# MAINfin2.net
KiCad netlist of a schematic drawn in EAGLE
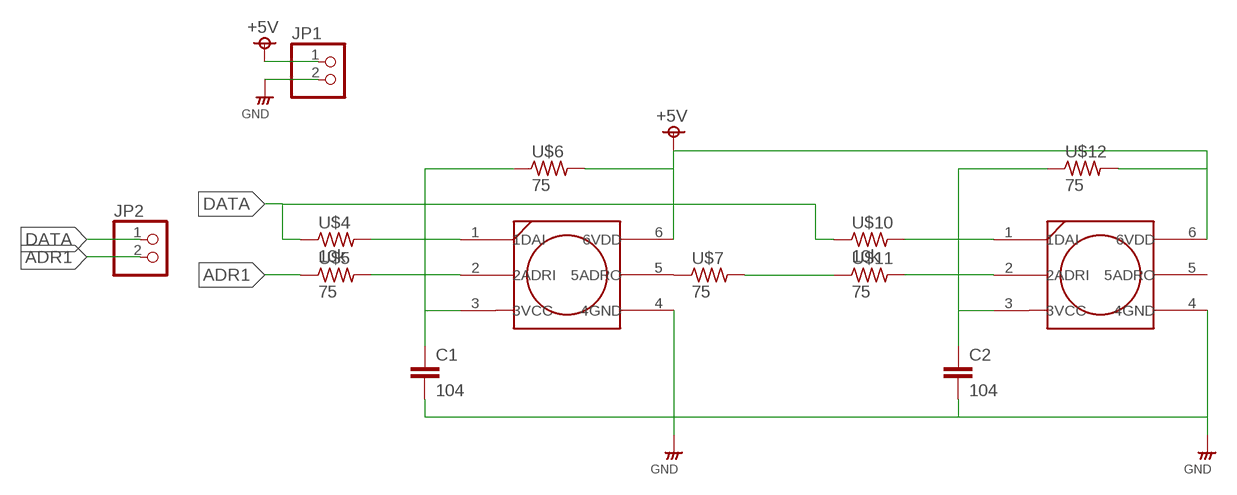
[diagram p0: schematic, sheet 1]

(export (version "E")
  (design (tool "Eeschema 10.0.6"))
  (components
    (comp (ref "C1")
      (value "104")
      (footprint "eagle-import:MLCC_25")
      (libsource (lib "eagle-import") (part "MLCC-2"))
    )
    (comp (ref "C2")
      (value "104")
      (footprint "eagle-import:MLCC_25")
      (libsource (lib "eagle-import") (part "MLCC-2"))
    )
    (comp (ref "JP1")
      (value "PINHD-1X2\"")
      (footprint "eagle-import:1_02")
      (libsource (lib "eagle-import") (part "PINHD-1X2{dblquote}"))
    )
    (comp (ref "JP2")
      (value "PINHD-1X2\"")
      (footprint "eagle-import:1_02")
      (libsource (lib "eagle-import") (part "PINHD-1X2{dblquote}"))
    )
    (comp (ref "U$1")
      (value "WS2822S")
      (footprint "eagle-import:WS2822S")
      (libsource (lib "eagle-import") (part "WS2822S"))
    )
    (comp (ref "U$4")
      (value "10k")
      (footprint "eagle-import:R_0.3")
      (libsource (lib "eagle-import") (part "RESISTORS-3"))
    )
    (comp (ref "U$5")
      (value "75")
      (footprint "eagle-import:R_0.3")
      (libsource (lib "eagle-import") (part "RESISTORS-3"))
    )
    (comp (ref "U$6")
      (value "75")
      (footprint "eagle-import:R_0.3")
      (libsource (lib "eagle-import") (part "RESISTORS-3"))
    )
    (comp (ref "U$7")
      (value "75")
      (footprint "eagle-import:R_0.3")
      (libsource (lib "eagle-import") (part "RESISTORS-3"))
    )
    (comp (ref "U$8")
      (value "WS2822S")
      (footprint "eagle-import:WS2822S")
      (libsource (lib "eagle-import") (part "WS2822S"))
    )
    (comp (ref "U$10")
      (value "10k")
      (footprint "eagle-import:R_0.3")
      (libsource (lib "eagle-import") (part "RESISTORS-3"))
    )
    (comp (ref "U$11")
      (value "75")
      (footprint "eagle-import:R_0.3")
      (libsource (lib "eagle-import") (part "RESISTORS-3"))
    )
    (comp (ref "U$12")
      (value "75")
      (footprint "eagle-import:R_0.3")
      (libsource (lib "eagle-import") (part "RESISTORS-3"))
    )
  )
  (nets
    (net (code "1") (name "/+5V") (class "Default")
      (node (ref "JP1") (pin "1") (pinfunction "1_1") (pintype "passive"))
      (node (ref "U$1") (pin "6") (pinfunction "6VDD_6") (pintype "bidirectional"))
      (node (ref "U$12") (pin "2") (pinfunction "2_2") (pintype "passive"))
      (node (ref "U$6") (pin "2") (pinfunction "2_2") (pintype "passive"))
      (node (ref "U$8") (pin "6") (pinfunction "6VDD_6") (pintype "bidirectional"))
    )
    (net (code "2") (name "ADR1") (class "Default")
      (node (ref "JP2") (pin "2") (pinfunction "2_2") (pintype "passive"))
      (node (ref "U$11") (pin "1") (pinfunction "1_1") (pintype "passive"))
      (node (ref "U$5") (pin "1") (pinfunction "1_1") (pintype "passive"))
      (node (ref "U$7") (pin "2") (pinfunction "2_2") (pintype "passive"))
    )
    (net (code "3") (name "DATA") (class "Default")
      (node (ref "JP2") (pin "1") (pinfunction "1_1") (pintype "passive"))
      (node (ref "U$10") (pin "1") (pinfunction "1_1") (pintype "passive"))
      (node (ref "U$4") (pin "1") (pinfunction "1_1") (pintype "passive"))
    )
    (net (code "4") (name "GND") (class "Default")
      (node (ref "C1") (pin "2") (pinfunction "2_2") (pintype "passive"))
      (node (ref "C2") (pin "2") (pinfunction "2_2") (pintype "passive"))
      (node (ref "JP1") (pin "2") (pinfunction "2_2") (pintype "passive"))
      (node (ref "U$1") (pin "4") (pinfunction "4GND_4") (pintype "bidirectional"))
      (node (ref "U$8") (pin "4") (pinfunction "4GND_4") (pintype "bidirectional"))
    )
    (net (code "5") (name "Net-(U$1-1DAI)") (class "Default")
      (node (ref "U$1") (pin "1") (pinfunction "1DAI_1") (pintype "bidirectional"))
      (node (ref "U$4") (pin "2") (pinfunction "2_2") (pintype "passive"))
    )
    (net (code "6") (name "Net-(U$1-2ADRI)") (class "Default")
      (node (ref "U$1") (pin "2") (pinfunction "2ADRI_2") (pintype "bidirectional"))
      (node (ref "U$5") (pin "2") (pinfunction "2_2") (pintype "passive"))
    )
    (net (code "7") (name "Net-(U$1-3VCC)") (class "Default")
      (node (ref "C1") (pin "1") (pinfunction "1_1") (pintype "passive"))
      (node (ref "U$1") (pin "3") (pinfunction "3VCC_3") (pintype "bidirectional"))
      (node (ref "U$6") (pin "1") (pinfunction "1_1") (pintype "passive"))
    )
    (net (code "8") (name "Net-(U$1-5ADRO)") (class "Default")
      (node (ref "U$1") (pin "5") (pinfunction "5ADRO_5") (pintype "bidirectional"))
      (node (ref "U$7") (pin "1") (pinfunction "1_1") (pintype "passive"))
    )
    (net (code "9") (name "Net-(U$8-1DAI)") (class "Default")
      (node (ref "U$10") (pin "2") (pinfunction "2_2") (pintype "passive"))
      (node (ref "U$8") (pin "1") (pinfunction "1DAI_1") (pintype "bidirectional"))
    )
    (net (code "10") (name "Net-(U$8-2ADRI)") (class "Default")
      (node (ref "U$11") (pin "2") (pinfunction "2_2") (pintype "passive"))
      (node (ref "U$8") (pin "2") (pinfunction "2ADRI_2") (pintype "bidirectional"))
    )
    (net (code "11") (name "Net-(U$8-3VCC)") (class "Default")
      (node (ref "C2") (pin "1") (pinfunction "1_1") (pintype "passive"))
      (node (ref "U$12") (pin "1") (pinfunction "1_1") (pintype "passive"))
      (node (ref "U$8") (pin "3") (pinfunction "3VCC_3") (pintype "bidirectional"))
    )
    (net (code "12") (name "unconnected-(U$8-5ADRO-Pad5)") (class "Default")
      (node (ref "U$8") (pin "5") (pinfunction "5ADRO_5") (pintype "bidirectional"))
    )
  )
)
